# SD_Card.net
KiCad netlist of a schematic drawn in Altium Designer
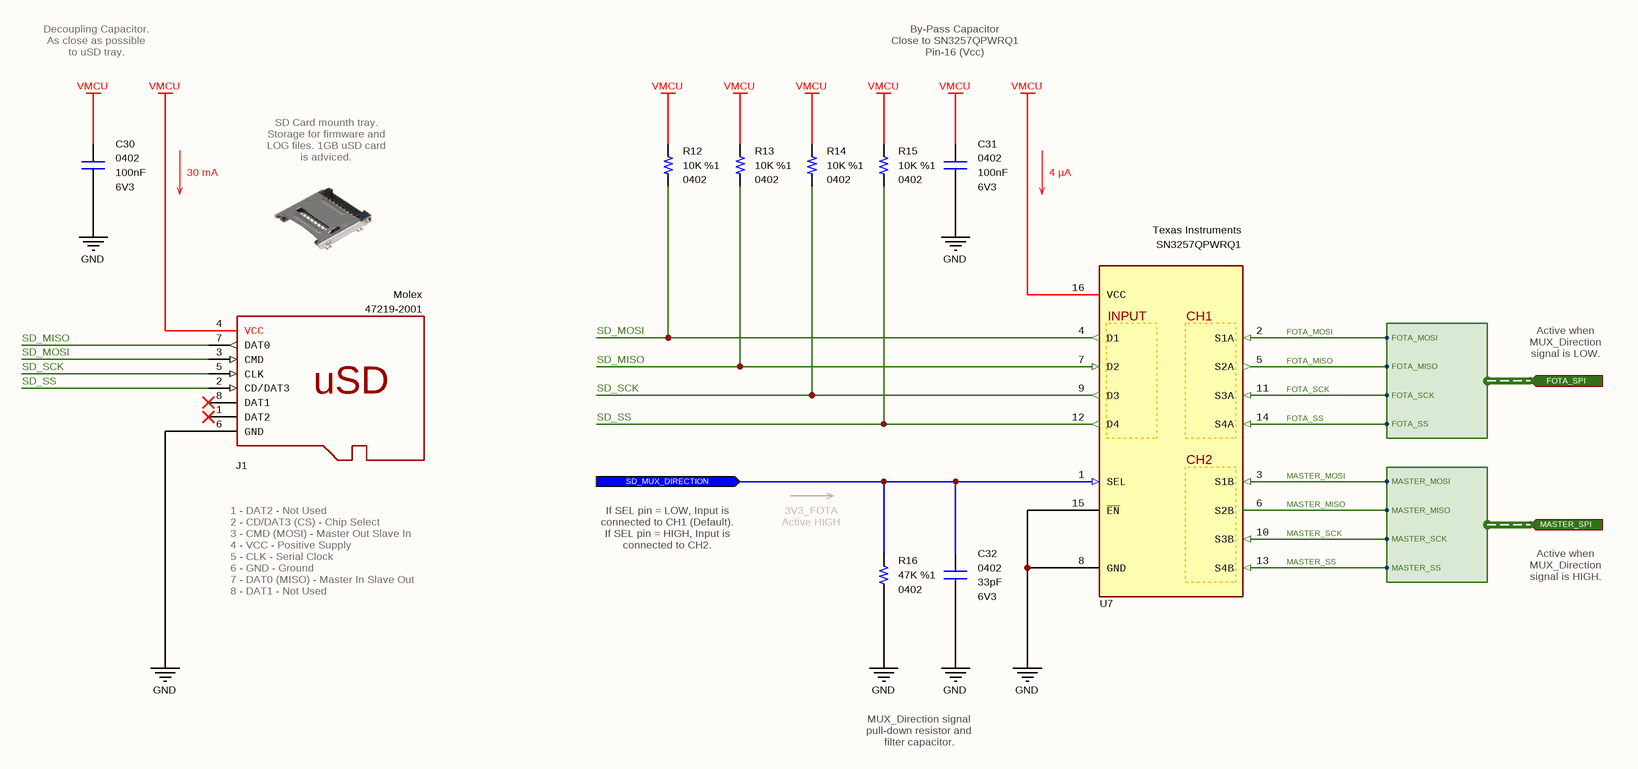
[diagram p0: SD Card.SchDoc]

(export (version "E")
  (design (tool "Eeschema 10.0.6"))
  (components
    (comp (ref "C30")
      (value "100nF")
      (footprint "CAPACITOR_0402")
      (description "Capacitor - 100nF [0402-6V3] (Ceramic)")
      (fields
        (field (name "TOLERANCE") "%10")
        (field (name "CASE") "0402")
        (field (name "VOLTAGE") "6V3")
        (field (name "MANUFACTURER PART NUMBER") "04026D104KAT4A")
      )
      (libsource (lib "Ovoo_Library") (part "Capacitor - 100nF [0402-6V3]"))
    )
    (comp (ref "C31")
      (value "100nF")
      (footprint "CAPACITOR_0402")
      (description "Capacitor - 100nF [0402-6V3] (Ceramic)")
      (fields
        (field (name "CASE") "0402")
        (field (name "TOLERANCE") "%10")
        (field (name "VOLTAGE") "6V3")
        (field (name "MANUFACTURER PART NUMBER") "04026D104KAT4A")
      )
      (libsource (lib "Ovoo_Library") (part "Capacitor - 100nF [0402-6V3]"))
    )
    (comp (ref "C32")
      (value "33pF")
      (footprint "CAPACITOR_0402")
      (description "Capacitor - 33pF [0402] (Ceramic)")
      (fields
        (field (name "TOLERANCE") "10%")
        (field (name "CASE") "0402")
        (field (name "VOLTAGE") "6V3")
        (field (name "MANUFACTURER PART NUMBER") "C0402C330J9RACAUTO")
      )
      (libsource (lib "Ovoo_Library") (part "Capacitor - 33pF [0402-6V3]"))
    )
    (comp (ref "J1")
      (value "Memory Card Connectors")
      (footprint "Connector - SD Module")
      (description "Memory Card Connectors TFR READER (HINGE TYPE)")
      (fields
        (field (name "MOUSER PART NUMBER") "538-47219-2001")
        (field (name "MANUFACTURER PART NUMBER") "47219-2001")
        (field (name "MANUFACTURER NAME") "Molex")
      )
      (libsource (lib "Ovoo_Library") (part "Connector - SD Slot"))
    )
    (comp (ref "R12")
      (value "10K")
      (footprint "RESISTOR_0402")
      (description "Thick Film Resistors - SMD 1/16 W 10 Kohms 1%")
      (fields
        (field (name "TOLERANCE") "%1")
        (field (name "CASE") "0402")
        (field (name "MANUFACTURER PART NUMBER") "CRCW040210K0FKED")
        (field (name "MOUSER PART NUMBER") "71-CRCW0402-10K-E3")
      )
      (libsource (lib "Ovoo_Library") (part "Resistor - 10K"))
    )
    (comp (ref "R13")
      (value "10K")
      (footprint "RESISTOR_0402")
      (description "Thick Film Resistors - SMD 1/16 W 10 Kohms 1%")
      (fields
        (field (name "TOLERANCE") "%1")
        (field (name "CASE") "0402")
        (field (name "MANUFACTURER PART NUMBER") "CRCW040210K0FKED")
        (field (name "MOUSER PART NUMBER") "71-CRCW0402-10K-E3")
      )
      (libsource (lib "Ovoo_Library") (part "Resistor - 10K"))
    )
    (comp (ref "R14")
      (value "10K")
      (footprint "RESISTOR_0402")
      (description "Thick Film Resistors - SMD 1/16 W 10 Kohms 1%")
      (fields
        (field (name "TOLERANCE") "%1")
        (field (name "CASE") "0402")
        (field (name "MANUFACTURER PART NUMBER") "CRCW040210K0FKED")
        (field (name "MOUSER PART NUMBER") "71-CRCW0402-10K-E3")
      )
      (libsource (lib "Ovoo_Library") (part "Resistor - 10K"))
    )
    (comp (ref "R15")
      (value "10K")
      (footprint "RESISTOR_0402")
      (description "Thick Film Resistors - SMD 1/16 W 10 Kohms 1%")
      (fields
        (field (name "TOLERANCE") "%1")
        (field (name "CASE") "0402")
        (field (name "MANUFACTURER PART NUMBER") "CRCW040210K0FKED")
        (field (name "MOUSER PART NUMBER") "71-CRCW0402-10K-E3")
      )
      (libsource (lib "Ovoo_Library") (part "Resistor - 10K"))
    )
    (comp (ref "R16")
      (value "47K")
      (footprint "RESISTOR_0402")
      (description "Thick Film Resistors - SMD 1/16 W 47 Kohms 1%")
      (fields
        (field (name "TOLERANCE") "%1")
        (field (name "CASE") "0402")
        (field (name "MANUFACTURER PART NUMBER") "CRCW040247K0FKED")
        (field (name "Comment") "47K - 0402 - %1 - 1/16W")
      )
      (libsource (lib "Ovoo_Library") (part "Resistor - 47K"))
    )
    (comp (ref "U7")
      (value "SPI Switch IC")
      (footprint "TSSOP-16")
      (description "Analogue Switch ICs 2:1 (SPDT), 4-channel switch with 1.8-V logic 16-TSSOP -40 to 125")
      (fields
        (field (name "MOUSER PART NUMBER") "595-SN3257QPWRQ1")
        (field (name "MANUFACTURER PART NUMBER") "SN3257QPWRQ1")
        (field (name "MANUFACTURER NAME") "Texas Instruments")
      )
      (libsource (lib "Ovoo_Library") (part "IC - SN3257QPWRQ1"))
    )
  )
  (nets
    (net (code "3") (name "/FOTA_MISO") (class "Default")
      (node (ref "U7") (pin "5") (pinfunction "S2A_5") (pintype "output"))
    )
    (net (code "4") (name "/FOTA_MOSI") (class "Default")
      (node (ref "U7") (pin "2") (pinfunction "S1A_2") (pintype "input"))
    )
    (net (code "5") (name "/FOTA_SCK") (class "Default")
      (node (ref "U7") (pin "11") (pinfunction "S3A_11") (pintype "input"))
    )
    (net (code "6") (name "/FOTA_SS") (class "Default")
      (node (ref "U7") (pin "14") (pinfunction "S4A_14") (pintype "input"))
    )
    (net (code "7") (name "/MASTER_MISO") (class "Default")
      (node (ref "U7") (pin "6") (pinfunction "S2B_6") (pintype "passive"))
    )
    (net (code "8") (name "/MASTER_MOSI") (class "Default")
      (node (ref "U7") (pin "3") (pinfunction "S1B_3") (pintype "input"))
    )
    (net (code "9") (name "/MASTER_SCK") (class "Default")
      (node (ref "U7") (pin "10") (pinfunction "S3B_10") (pintype "input"))
    )
    (net (code "10") (name "/MASTER_SS") (class "Default")
      (node (ref "U7") (pin "13") (pinfunction "S4B_13") (pintype "input"))
    )
    (net (code "11") (name "/SD_MISO") (class "Default")
      (node (ref "J1") (pin "7") (pinfunction "DAT0_7") (pintype "output"))
      (node (ref "R13") (pin "1") (pinfunction "1_1") (pintype "passive"))
      (node (ref "U7") (pin "7") (pinfunction "D2_7") (pintype "input"))
    )
    (net (code "12") (name "/SD_MOSI") (class "Default")
      (node (ref "J1") (pin "3") (pinfunction "CMD_3") (pintype "input"))
      (node (ref "R12") (pin "1") (pinfunction "1_1") (pintype "passive"))
      (node (ref "U7") (pin "4") (pinfunction "D1_4") (pintype "output"))
    )
    (net (code "13") (name "/SD_MUX_DIRECTION") (class "Default")
      (node (ref "C32") (pin "2") (pinfunction "2_2") (pintype "passive"))
      (node (ref "R16") (pin "2") (pinfunction "2_2") (pintype "passive"))
      (node (ref "U7") (pin "1") (pinfunction "SEL_1") (pintype "input"))
    )
    (net (code "14") (name "/SD_SCK") (class "Default")
      (node (ref "J1") (pin "5") (pinfunction "CLK_5") (pintype "input"))
      (node (ref "R14") (pin "1") (pinfunction "1_1") (pintype "passive"))
      (node (ref "U7") (pin "9") (pinfunction "D3_9") (pintype "output"))
    )
    (net (code "15") (name "/SD_SS") (class "Default")
      (node (ref "J1") (pin "2") (pinfunction "CD/DAT3_2") (pintype "input"))
      (node (ref "R15") (pin "1") (pinfunction "1_1") (pintype "passive"))
      (node (ref "U7") (pin "12") (pinfunction "D4_12") (pintype "output"))
    )
    (net (code "18") (name "GND") (class "Default")
      (node (ref "C30") (pin "1") (pinfunction "1_1") (pintype "passive"))
      (node (ref "C31") (pin "2") (pinfunction "2_2") (pintype "passive"))
      (node (ref "C32") (pin "1") (pinfunction "1_1") (pintype "passive"))
      (node (ref "J1") (pin "6") (pinfunction "GND_6") (pintype "passive"))
      (node (ref "R16") (pin "1") (pinfunction "1_1") (pintype "passive"))
      (node (ref "U7") (pin "15") (pinfunction "~{EN}_15") (pintype "power_in"))
      (node (ref "U7") (pin "8") (pinfunction "GND_8") (pintype "power_in"))
    )
    (net (code "19") (name "VMCU") (class "Default")
      (node (ref "C30") (pin "2") (pinfunction "2_2") (pintype "passive"))
      (node (ref "C31") (pin "1") (pinfunction "1_1") (pintype "passive"))
      (node (ref "J1") (pin "4") (pinfunction "VCC_4") (pintype "passive"))
      (node (ref "R12") (pin "2") (pinfunction "2_2") (pintype "passive"))
      (node (ref "R13") (pin "2") (pinfunction "2_2") (pintype "passive"))
      (node (ref "R14") (pin "2") (pinfunction "2_2") (pintype "passive"))
      (node (ref "R15") (pin "2") (pinfunction "2_2") (pintype "passive"))
      (node (ref "U7") (pin "16") (pinfunction "VCC_16") (pintype "power_in"))
    )
    (net (code "20") (name "unconnected-(J1-DAT1-Pad8)") (class "Default")
      (node (ref "J1") (pin "8") (pinfunction "DAT1_8") (pintype "passive+no_connect"))
    )
    (net (code "21") (name "unconnected-(J1-DAT2-Pad1)") (class "Default")
      (node (ref "J1") (pin "1") (pinfunction "DAT2_1") (pintype "passive+no_connect"))
    )
  )
)
